# ATMega328P-PU.net
KiCad netlist of a schematic drawn in Altium Designer
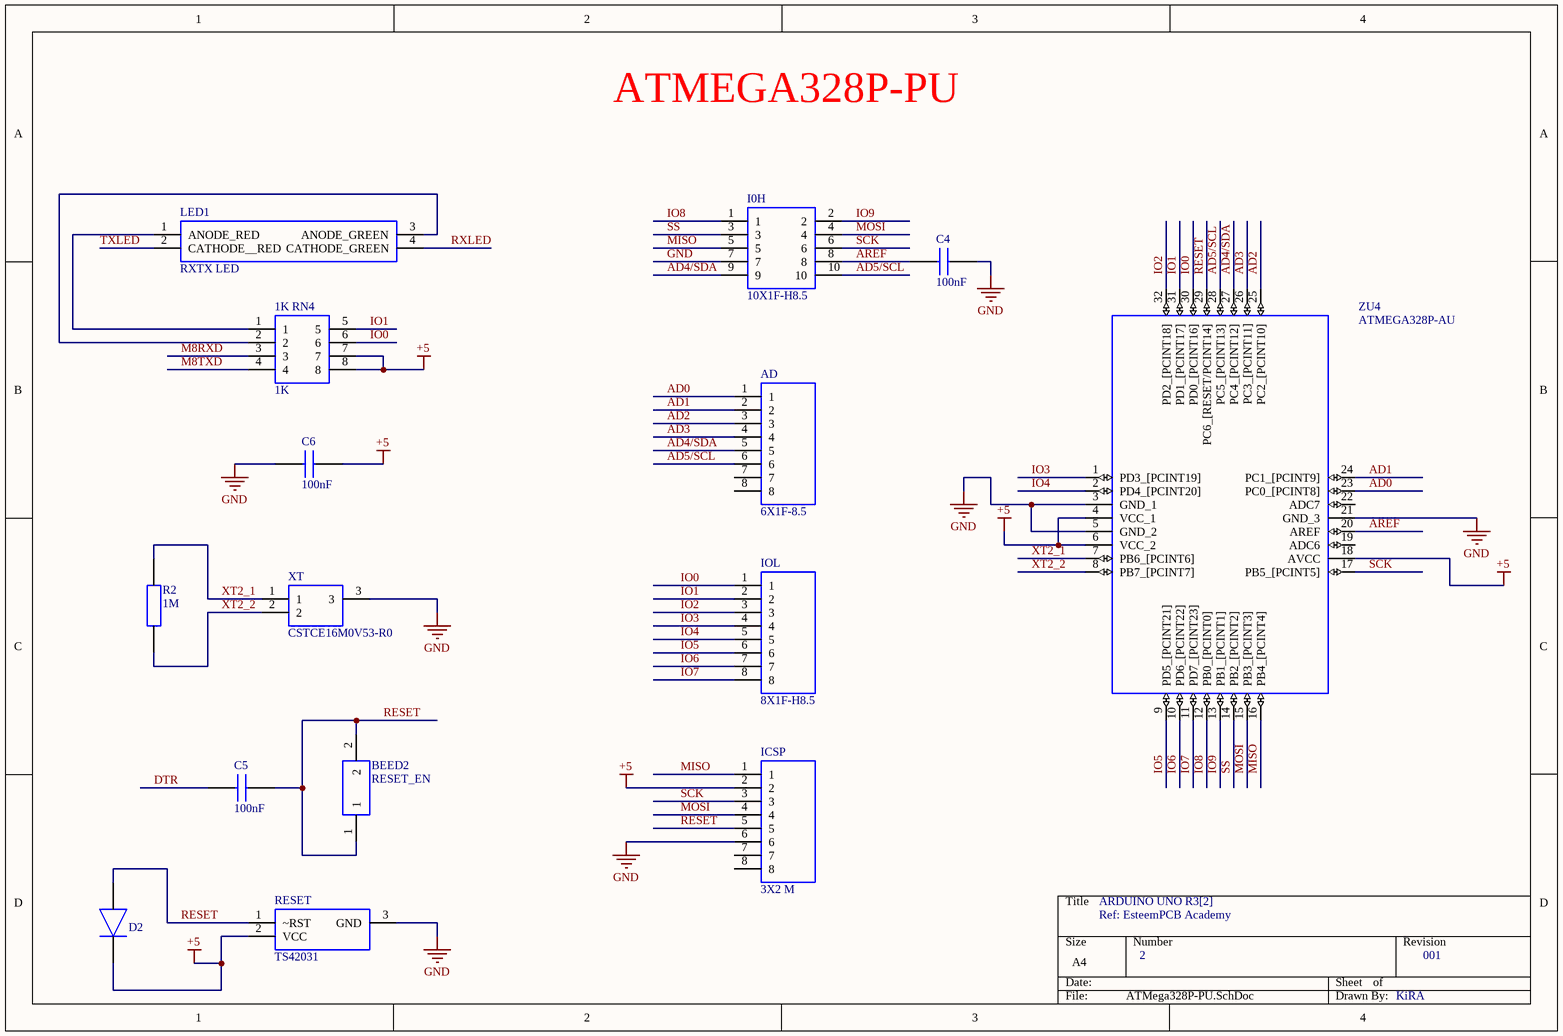
[diagram p0: ATMega328P-PU.SchDoc]

(export (version "E")
  (design (tool "Eeschema 10.0.6"))
  (components
    (comp (ref "1K RN4")
      (value "1K")
      (footprint "CAY10-XXXJ4")
      (fields
        (field (name "MANUFACTURER_PART_NUMBER") "CAY10-220J4LF")
        (field (name "RS PART NUMBER") "1674746")
        (field (name "MOUSER PART NUMBER") "652-CAY10-220J4LF")
      )
      (libsource (lib "1K RN2C") (part "CAY10-220J4LF"))
    )
    (comp (ref "AD")
      (value "6X1F-8.5")
      (footprint "HDRV8W90P0X254_1X8_2032X249X560P")
      (fields
        (field (name "MANUFACTURER_PART_NUMBER") "90120-0768")
        (field (name "RS PART NUMBER") "1671900")
        (field (name "MOUSER PART NUMBER") "538-90120-0768")
      )
      (libsource (lib "6X1F-H8.5") (part "90120-0768"))
    )
    (comp (ref "BEED2")
      (value "RESET_EN")
      (footprint "BEADC2012X105N")
      (description "Chip Ferrite Bead 600R 0805 300mA 1LN")
      (fields
        (field (name "MANUFACTURER_PART_NUMBER") "BLM21BD601SH1D")
        (field (name "RS PART NUMBER") "1048541P")
      )
      (libsource (lib "Ferride Bead") (part "BLM21BD601SH1D"))
    )
    (comp (ref "C4")
      (value "100nF")
      (footprint "CAPC2012X130N")
      (fields
        (field (name "MANUFACTURER_PART_NUMBER") "0805Y0500104KXT")
        (field (name "RS PART NUMBER") "7738389P")
      )
      (libsource (lib "100nF") (part "0805Y0500104KXT"))
    )
    (comp (ref "C5")
      (value "100nF")
      (footprint "CAPC2012X130N")
      (fields
        (field (name "MANUFACTURER_PART_NUMBER") "0805Y0500104KXT")
        (field (name "RS PART NUMBER") "7738389P")
      )
      (libsource (lib "100nF") (part "0805Y0500104KXT"))
    )
    (comp (ref "C6")
      (value "100nF")
      (footprint "CAPC2012X130N")
      (fields
        (field (name "MANUFACTURER_PART_NUMBER") "0805Y0500104KXT")
        (field (name "RS PART NUMBER") "7738389P")
      )
      (libsource (lib "100nF") (part "0805Y0500104KXT"))
    )
    (comp (ref "D2")
      (value "CD1206-S01575")
      (footprint "DIOC3016X65N")
      (fields
        (field (name "RS PART NUMBER") "1775431")
        (field (name "MOUSER PART NUMBER") "652-CD1206-S01575")
      )
      (libsource (lib "CD1206-S01575") (part "CD1206-S01575"))
    )
    (comp (ref "I0H")
      (value "10X1F-H8.5")
      (footprint "FTMH10503LDV")
      (fields
        (field (name "MANUFACTURER_PART_NUMBER") "FTMH-105-03-L-DV")
        (field (name "RS PART NUMBER") "7668984P")
        (field (name "MOUSER PART NUMBER") "200-FTMH10503LDV")
      )
      (libsource (lib "10X1F-H8.5") (part "FTMH-105-03-L-DV"))
    )
    (comp (ref "ICSP")
      (value "3X2 M")
      (footprint "HDRV8W90P0X254_1X8_2032X249X560P")
      (fields
        (field (name "MANUFACTURER_PART_NUMBER") "90120-0768")
        (field (name "RS PART NUMBER") "1671900")
        (field (name "MOUSER PART NUMBER") "538-90120-0768")
      )
      (libsource (lib "3x2 Male con") (part "90120-0768"))
    )
    (comp (ref "IOL")
      (value "8X1F-H8.5")
      (footprint "HDRV8W90P0X254_1X8_2032X249X560P")
      (fields
        (field (name "MANUFACTURER_PART_NUMBER") "90120-0768")
        (field (name "RS PART NUMBER") "1671900")
        (field (name "MOUSER PART NUMBER") "538-90120-0768")
      )
      (libsource (lib "8X1F-H8.5") (part "90120-0768"))
    )
    (comp (ref "LED1")
      (value "RXTX LED")
      (footprint "SML522MD8WT86")
      (fields
        (field (name "MANUFACTURER_PART_NUMBER") "SML-522MU8WT86")
        (field (name "RS PART NUMBER") "1682468")
        (field (name "MOUSER PART NUMBER") "755-SML-522MU8WT86")
      )
      (libsource (lib "Yellow LED") (part "SML-522MU8WT86"))
    )
    (comp (ref "R2")
      (value "1M")
      (footprint "RESC1608X55N")
      (description "TE CONNECTIVITY - CPF0603B1M0E1 - RES, THIN FILM, 1M, 0.1%, 0.063W, 0603")
      (fields
        (field (name "MANUFACTURER_PART_NUMBER") "CPF0603B1M0E1")
        (field (name "MOUSER PART NUMBER") "279-CPF0603B1M0E1")
      )
      (libsource (lib "1MR") (part "CPF0603B1M0E1"))
    )
    (comp (ref "RESET")
      (value "TS42031")
      (footprint "SOT95P240X110-3N")
      (description "3.3V EconoReset with Pushbutton")
      (fields (field (name "MANUFACTURER_PART_NUMBER") "DS1818R-5+"))
      (libsource (lib "TS42031-160R-TR-7260") (part "DS1818R-5+"))
    )
    (comp (ref "XT")
      (value "CSTCE16M0V53-R0")
      (footprint "CSTCE-V")
      (fields
        (field (name "RS PART NUMBER") "7926524P")
        (field (name "MOUSER PART NUMBER") "81-CSTCE16M0V53-R0")
      )
      (libsource (lib "CSTCE16M0V53-R0") (part "CSTCE16M0V53-R0"))
    )
    (comp (ref "ZU4")
      (value "ATMEGA328P-AU")
      (footprint "QFP80P900X900X120-32N")
      (description "MICROCHIP - ATMEGA328P-AU. - MICROCONTROLLER MCU, 8 BIT, ATMEGA, 20MHZ, TQFP-32")
      (fields
        (field (name "RS PART NUMBER") "1310271")
        (field (name "MOUSER PART NUMBER") "556-ATMEGA328P-AU")
      )
      (libsource (lib "ATMega328P-PU") (part "ATMEGA328P-AU"))
    )
  )
  (nets
    (net (code "1") (name "+5") (class "Default")
      (node (ref "1K RN4") (pin "7") (pinfunction "7_7") (pintype "passive"))
      (node (ref "1K RN4") (pin "8") (pinfunction "8_8") (pintype "passive"))
      (node (ref "C6") (pin "2") (pinfunction "2_2") (pintype "passive"))
      (node (ref "D2") (pin "1") (pinfunction "K_1") (pintype "passive"))
      (node (ref "ICSP") (pin "2") (pinfunction "2_2") (pintype "passive"))
      (node (ref "RESET") (pin "2") (pinfunction "VCC_2") (pintype "passive"))
      (node (ref "ZU4") (pin "18") (pinfunction "AVCC_18") (pintype "power_in"))
      (node (ref "ZU4") (pin "4") (pinfunction "VCC_1_4") (pintype "power_in"))
      (node (ref "ZU4") (pin "6") (pinfunction "VCC_2_6") (pintype "power_in"))
    )
    (net (code "2") (name "/AD0") (class "Default")
      (node (ref "AD") (pin "1") (pinfunction "1_1") (pintype "passive"))
      (node (ref "ZU4") (pin "23") (pinfunction "PC0_[PCINT8]_23") (pintype "bidirectional"))
    )
    (net (code "3") (name "/AD1") (class "Default")
      (node (ref "AD") (pin "2") (pinfunction "2_2") (pintype "passive"))
      (node (ref "ZU4") (pin "24") (pinfunction "PC1_[PCINT9]_24") (pintype "bidirectional"))
    )
    (net (code "4") (name "/AD2") (class "Default")
      (node (ref "AD") (pin "3") (pinfunction "3_3") (pintype "passive"))
      (node (ref "ZU4") (pin "25") (pinfunction "PC2_[PCINT10]_25") (pintype "bidirectional"))
    )
    (net (code "5") (name "/AD3") (class "Default")
      (node (ref "AD") (pin "4") (pinfunction "4_4") (pintype "passive"))
      (node (ref "ZU4") (pin "26") (pinfunction "PC3_[PCINT11]_26") (pintype "bidirectional"))
    )
    (net (code "6") (name "/AD4{slash}SDA") (class "Default")
      (node (ref "AD") (pin "5") (pinfunction "5_5") (pintype "passive"))
      (node (ref "I0H") (pin "9") (pinfunction "9_9") (pintype "passive"))
      (node (ref "ZU4") (pin "27") (pinfunction "PC4_[PCINT12]_27") (pintype "bidirectional"))
    )
    (net (code "7") (name "/AD5{slash}SCL") (class "Default")
      (node (ref "AD") (pin "6") (pinfunction "6_6") (pintype "passive"))
      (node (ref "I0H") (pin "10") (pinfunction "10_10") (pintype "passive"))
      (node (ref "ZU4") (pin "28") (pinfunction "PC5_[PCINT13]_28") (pintype "bidirectional"))
    )
    (net (code "8") (name "/AREF") (class "Default")
      (node (ref "C4") (pin "1") (pinfunction "1_1") (pintype "passive"))
      (node (ref "I0H") (pin "8") (pinfunction "8_8") (pintype "passive"))
      (node (ref "ZU4") (pin "20") (pinfunction "AREF_20") (pintype "bidirectional"))
    )
    (net (code "9") (name "/DTR") (class "Default")
      (node (ref "C5") (pin "1") (pinfunction "1_1") (pintype "passive"))
    )
    (net (code "10") (name "/IO0") (class "Default")
      (node (ref "1K RN4") (pin "6") (pinfunction "6_6") (pintype "passive"))
      (node (ref "IOL") (pin "1") (pinfunction "1_1") (pintype "passive"))
      (node (ref "ZU4") (pin "30") (pinfunction "PD0_[PCINT16]_30") (pintype "bidirectional"))
    )
    (net (code "11") (name "/IO1") (class "Default")
      (node (ref "1K RN4") (pin "5") (pinfunction "5_5") (pintype "passive"))
      (node (ref "IOL") (pin "2") (pinfunction "2_2") (pintype "passive"))
      (node (ref "ZU4") (pin "31") (pinfunction "PD1_[PCINT17]_31") (pintype "bidirectional"))
    )
    (net (code "12") (name "/IO2") (class "Default")
      (node (ref "IOL") (pin "3") (pinfunction "3_3") (pintype "passive"))
      (node (ref "ZU4") (pin "32") (pinfunction "PD2_[PCINT18]_32") (pintype "bidirectional"))
    )
    (net (code "13") (name "/IO3") (class "Default")
      (node (ref "IOL") (pin "4") (pinfunction "4_4") (pintype "passive"))
      (node (ref "ZU4") (pin "1") (pinfunction "PD3_[PCINT19]_1") (pintype "bidirectional"))
    )
    (net (code "14") (name "/IO4") (class "Default")
      (node (ref "IOL") (pin "5") (pinfunction "5_5") (pintype "passive"))
      (node (ref "ZU4") (pin "2") (pinfunction "PD4_[PCINT20]_2") (pintype "bidirectional"))
    )
    (net (code "15") (name "/IO5") (class "Default")
      (node (ref "IOL") (pin "6") (pinfunction "6_6") (pintype "passive"))
      (node (ref "ZU4") (pin "9") (pinfunction "PD5_[PCINT21]_9") (pintype "bidirectional"))
    )
    (net (code "16") (name "/IO6") (class "Default")
      (node (ref "IOL") (pin "7") (pinfunction "7_7") (pintype "passive"))
      (node (ref "ZU4") (pin "10") (pinfunction "PD6_[PCINT22]_10") (pintype "bidirectional"))
    )
    (net (code "17") (name "/IO7") (class "Default")
      (node (ref "IOL") (pin "8") (pinfunction "8_8") (pintype "passive"))
      (node (ref "ZU4") (pin "11") (pinfunction "PD7_[PCINT23]_11") (pintype "bidirectional"))
    )
    (net (code "18") (name "/IO8") (class "Default")
      (node (ref "I0H") (pin "1") (pinfunction "1_1") (pintype "passive"))
      (node (ref "ZU4") (pin "12") (pinfunction "PB0_[PCINT0]_12") (pintype "bidirectional"))
    )
    (net (code "19") (name "/IO9") (class "Default")
      (node (ref "I0H") (pin "2") (pinfunction "2_2") (pintype "passive"))
      (node (ref "ZU4") (pin "13") (pinfunction "PB1_[PCINT1]_13") (pintype "bidirectional"))
    )
    (net (code "20") (name "/M8RXD") (class "Default")
      (node (ref "1K RN4") (pin "3") (pinfunction "3_3") (pintype "passive"))
    )
    (net (code "21") (name "/M8TXD") (class "Default")
      (node (ref "1K RN4") (pin "4") (pinfunction "4_4") (pintype "passive"))
    )
    (net (code "22") (name "/MISO") (class "Default")
      (node (ref "I0H") (pin "5") (pinfunction "5_5") (pintype "passive"))
      (node (ref "ICSP") (pin "1") (pinfunction "1_1") (pintype "passive"))
      (node (ref "ZU4") (pin "16") (pinfunction "PB4_[PCINT4]_16") (pintype "bidirectional"))
    )
    (net (code "23") (name "/MOSI") (class "Default")
      (node (ref "I0H") (pin "4") (pinfunction "4_4") (pintype "passive"))
      (node (ref "ICSP") (pin "4") (pinfunction "4_4") (pintype "passive"))
      (node (ref "ZU4") (pin "15") (pinfunction "PB3_[PCINT3]_15") (pintype "bidirectional"))
    )
    (net (code "24") (name "/RESET") (class "Default")
      (node (ref "BEED2") (pin "1") (pinfunction "1_1") (pintype "passive"))
      (node (ref "BEED2") (pin "2") (pinfunction "2_2") (pintype "passive"))
      (node (ref "C5") (pin "2") (pinfunction "2_2") (pintype "passive"))
      (node (ref "D2") (pin "2") (pinfunction "A_2") (pintype "passive"))
      (node (ref "ICSP") (pin "5") (pinfunction "5_5") (pintype "passive"))
      (node (ref "RESET") (pin "1") (pinfunction "~RST_1") (pintype "passive"))
      (node (ref "ZU4") (pin "29") (pinfunction "PC6_[RESET/PCINT14]_29") (pintype "bidirectional"))
    )
    (net (code "25") (name "/RXLED") (class "Default")
      (node (ref "LED1") (pin "4") (pinfunction "CATHODE_GREEN_4") (pintype "passive"))
    )
    (net (code "26") (name "/SCK") (class "Default")
      (node (ref "I0H") (pin "6") (pinfunction "6_6") (pintype "passive"))
      (node (ref "ICSP") (pin "3") (pinfunction "3_3") (pintype "passive"))
      (node (ref "ZU4") (pin "17") (pinfunction "PB5_[PCINT5]_17") (pintype "bidirectional"))
    )
    (net (code "27") (name "/SS") (class "Default")
      (node (ref "I0H") (pin "3") (pinfunction "3_3") (pintype "passive"))
      (node (ref "ZU4") (pin "14") (pinfunction "PB2_[PCINT2]_14") (pintype "bidirectional"))
    )
    (net (code "28") (name "/TXLED") (class "Default")
      (node (ref "LED1") (pin "2") (pinfunction "CATHODE__RED_2") (pintype "passive"))
    )
    (net (code "29") (name "/XT2_1") (class "Default")
      (node (ref "R2") (pin "2") (pinfunction "2_2") (pintype "passive"))
      (node (ref "XT") (pin "1") (pinfunction "1_1") (pintype "passive"))
      (node (ref "ZU4") (pin "7") (pinfunction "PB6_[PCINT6]_7") (pintype "bidirectional"))
    )
    (net (code "30") (name "/XT2_2") (class "Default")
      (node (ref "R2") (pin "1") (pinfunction "1_1") (pintype "passive"))
      (node (ref "XT") (pin "2") (pinfunction "2_2") (pintype "passive"))
      (node (ref "ZU4") (pin "8") (pinfunction "PB7_[PCINT7]_8") (pintype "bidirectional"))
    )
    (net (code "31") (name "GND") (class "Default")
      (node (ref "C4") (pin "2") (pinfunction "2_2") (pintype "passive"))
      (node (ref "C6") (pin "1") (pinfunction "1_1") (pintype "passive"))
      (node (ref "I0H") (pin "7") (pinfunction "7_7") (pintype "passive"))
      (node (ref "ICSP") (pin "6") (pinfunction "6_6") (pintype "passive"))
      (node (ref "RESET") (pin "3") (pinfunction "GND_3") (pintype "passive"))
      (node (ref "XT") (pin "3") (pinfunction "3_3") (pintype "passive"))
      (node (ref "ZU4") (pin "21") (pinfunction "GND_3_21") (pintype "passive"))
      (node (ref "ZU4") (pin "3") (pinfunction "GND_1_3") (pintype "passive"))
      (node (ref "ZU4") (pin "5") (pinfunction "GND_2_5") (pintype "passive"))
    )
    (net (code "32") (name "Net-(LED1-ANODE_GREEN)") (class "Default")
      (node (ref "1K RN4") (pin "2") (pinfunction "2_2") (pintype "passive"))
      (node (ref "LED1") (pin "3") (pinfunction "ANODE_GREEN_3") (pintype "passive"))
    )
    (net (code "33") (name "Net-(LED1-ANODE_RED)") (class "Default")
      (node (ref "1K RN4") (pin "1") (pinfunction "1_1") (pintype "passive"))
      (node (ref "LED1") (pin "1") (pinfunction "ANODE_RED_1") (pintype "passive"))
    )
    (net (code "34") (name "unconnected-(AD-Pad7)") (class "Default")
      (node (ref "AD") (pin "7") (pinfunction "7_7") (pintype "passive"))
    )
    (net (code "35") (name "unconnected-(AD-Pad8)") (class "Default")
      (node (ref "AD") (pin "8") (pinfunction "8_8") (pintype "passive"))
    )
    (net (code "36") (name "unconnected-(ICSP-Pad7)") (class "Default")
      (node (ref "ICSP") (pin "7") (pinfunction "7_7") (pintype "passive"))
    )
    (net (code "37") (name "unconnected-(ICSP-Pad8)") (class "Default")
      (node (ref "ICSP") (pin "8") (pinfunction "8_8") (pintype "passive"))
    )
    (net (code "38") (name "unconnected-(ZU4-ADC6-Pad19)") (class "Default")
      (node (ref "ZU4") (pin "19") (pinfunction "ADC6_19") (pintype "bidirectional"))
    )
    (net (code "39") (name "unconnected-(ZU4-ADC7-Pad22)") (class "Default")
      (node (ref "ZU4") (pin "22") (pinfunction "ADC7_22") (pintype "bidirectional"))
    )
  )
)
